# Llave_analogica.net
KiCad netlist of a schematic drawn in Altium Designer
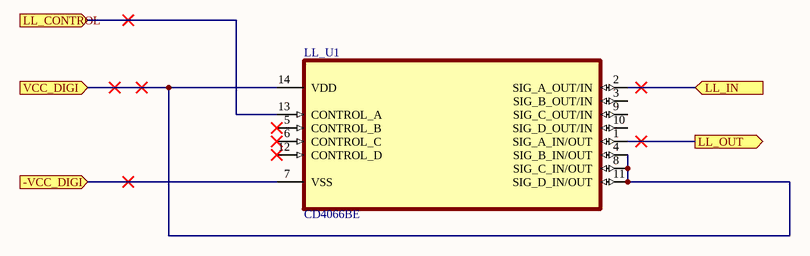
[diagram p0: Llave_analogica.SchDoc]

(export (version "E")
  (design (tool "Eeschema 10.0.6"))
  (components
    (comp (ref "LL_U1")
      (value "CD4066BE")
      (footprint "DIP254P762X508-14")
      (description "Bilateral, FET Switches 1 x 1:1 14-PDIP")
      (fields (field (name "MF") "Texas Instruments"))
      (libsource (lib "CD4066BE") (part "CD4066BE"))
    )
  )
  (nets
    (net (code "1") (name "/-VCC_DIGI") (class "Default")
      (node (ref "LL_U1") (pin "7") (pinfunction "VSS_7") (pintype "passive"))
    )
    (net (code "2") (name "/LL_CONTROL") (class "Default")
      (node (ref "LL_U1") (pin "13") (pinfunction "CONTROL_A_13") (pintype "input"))
    )
    (net (code "3") (name "/LL_IN") (class "Default")
      (node (ref "LL_U1") (pin "2") (pinfunction "SIG_A_OUT/IN_2") (pintype "bidirectional"))
    )
    (net (code "4") (name "/LL_OUT") (class "Default")
      (node (ref "LL_U1") (pin "1") (pinfunction "SIG_A_IN/OUT_1") (pintype "bidirectional"))
    )
    (net (code "5") (name "/VCC_DIGI") (class "Default")
      (node (ref "LL_U1") (pin "11") (pinfunction "SIG_D_IN/OUT_11") (pintype "bidirectional"))
      (node (ref "LL_U1") (pin "14") (pinfunction "VDD_14") (pintype "power_in"))
      (node (ref "LL_U1") (pin "4") (pinfunction "SIG_B_IN/OUT_4") (pintype "bidirectional"))
      (node (ref "LL_U1") (pin "8") (pinfunction "SIG_C_IN/OUT_8") (pintype "bidirectional"))
    )
    (net (code "6") (name "unconnected-(LL_U1-CONTROL_B-Pad5)") (class "Default")
      (node (ref "LL_U1") (pin "5") (pinfunction "CONTROL_B_5") (pintype "input+no_connect"))
    )
    (net (code "7") (name "unconnected-(LL_U1-CONTROL_C-Pad6)") (class "Default")
      (node (ref "LL_U1") (pin "6") (pinfunction "CONTROL_C_6") (pintype "input+no_connect"))
    )
    (net (code "8") (name "unconnected-(LL_U1-CONTROL_D-Pad12)") (class "Default")
      (node (ref "LL_U1") (pin "12") (pinfunction "CONTROL_D_12") (pintype "input+no_connect"))
    )
    (net (code "9") (name "unconnected-(LL_U1-SIG_B_OUT{slash}IN-Pad3)") (class "Default")
      (node (ref "LL_U1") (pin "3") (pinfunction "SIG_B_OUT/IN_3") (pintype "bidirectional"))
    )
    (net (code "10") (name "unconnected-(LL_U1-SIG_C_OUT{slash}IN-Pad9)") (class "Default")
      (node (ref "LL_U1") (pin "9") (pinfunction "SIG_C_OUT/IN_9") (pintype "bidirectional"))
    )
    (net (code "11") (name "unconnected-(LL_U1-SIG_D_OUT{slash}IN-Pad10)") (class "Default")
      (node (ref "LL_U1") (pin "10") (pinfunction "SIG_D_OUT/IN_10") (pintype "bidirectional"))
    )
  )
)
